# tally-controller-shield.net
KiCad netlist of a schematic drawn in EAGLE
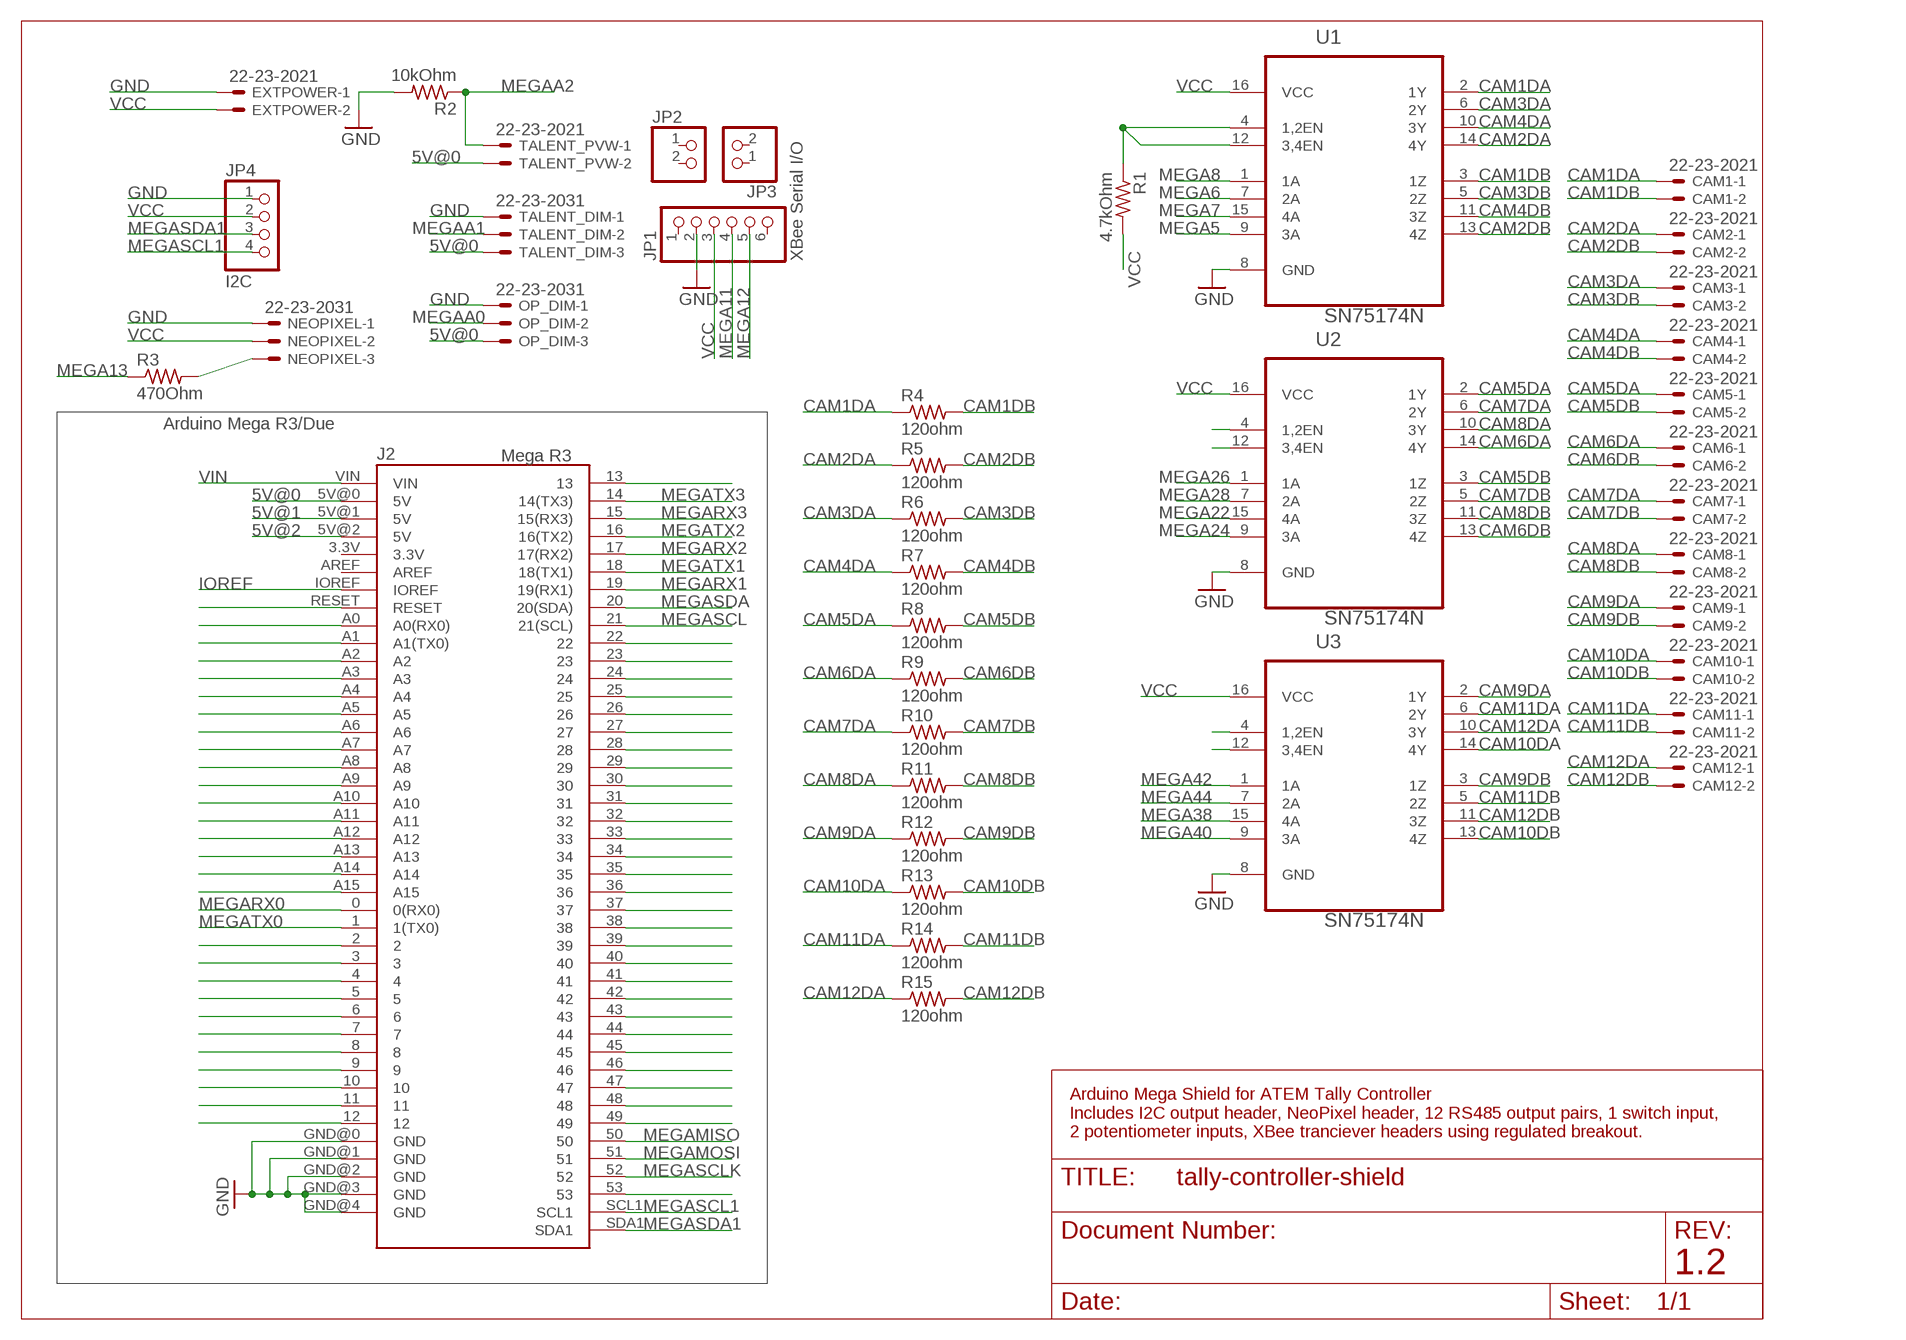
[diagram p0: schematic, sheet 1]

(export (version "E")
  (design (tool "Eeschema 10.0.6"))
  (components
    (comp (ref "CAM1")
      (value "22-23-2021")
      (footprint "eagle-import:22-23-2021")
      (fields (field (name "MF") "MOLEX"))
      (libsource (lib "eagle-import") (part "22-23-2021"))
    )
    (comp (ref "CAM2")
      (value "22-23-2021")
      (footprint "eagle-import:22-23-2021")
      (fields (field (name "MF") "MOLEX"))
      (libsource (lib "eagle-import") (part "22-23-2021"))
    )
    (comp (ref "CAM3")
      (value "22-23-2021")
      (footprint "eagle-import:22-23-2021")
      (fields (field (name "MF") "MOLEX"))
      (libsource (lib "eagle-import") (part "22-23-2021"))
    )
    (comp (ref "CAM4")
      (value "22-23-2021")
      (footprint "eagle-import:22-23-2021")
      (fields (field (name "MF") "MOLEX"))
      (libsource (lib "eagle-import") (part "22-23-2021"))
    )
    (comp (ref "CAM5")
      (value "22-23-2021")
      (footprint "eagle-import:22-23-2021")
      (fields (field (name "MF") "MOLEX"))
      (libsource (lib "eagle-import") (part "22-23-2021"))
    )
    (comp (ref "CAM6")
      (value "22-23-2021")
      (footprint "eagle-import:22-23-2021")
      (fields (field (name "MF") "MOLEX"))
      (libsource (lib "eagle-import") (part "22-23-2021"))
    )
    (comp (ref "CAM7")
      (value "22-23-2021")
      (footprint "eagle-import:22-23-2021")
      (fields (field (name "MF") "MOLEX"))
      (libsource (lib "eagle-import") (part "22-23-2021"))
    )
    (comp (ref "CAM8")
      (value "22-23-2021")
      (footprint "eagle-import:22-23-2021")
      (fields (field (name "MF") "MOLEX"))
      (libsource (lib "eagle-import") (part "22-23-2021"))
    )
    (comp (ref "CAM9")
      (value "22-23-2021")
      (footprint "eagle-import:22-23-2021")
      (fields (field (name "MF") "MOLEX"))
      (libsource (lib "eagle-import") (part "22-23-2021"))
    )
    (comp (ref "CAM10")
      (value "22-23-2021")
      (footprint "eagle-import:22-23-2021")
      (fields (field (name "MF") "MOLEX"))
      (libsource (lib "eagle-import") (part "22-23-2021"))
    )
    (comp (ref "CAM11")
      (value "22-23-2021")
      (footprint "eagle-import:22-23-2021")
      (fields (field (name "MF") "MOLEX"))
      (libsource (lib "eagle-import") (part "22-23-2021"))
    )
    (comp (ref "CAM12")
      (value "22-23-2021")
      (footprint "eagle-import:22-23-2021")
      (fields (field (name "MF") "MOLEX"))
      (libsource (lib "eagle-import") (part "22-23-2021"))
    )
    (comp (ref "EXTPOWER")
      (value "22-23-2021")
      (footprint "eagle-import:22-23-2021")
      (fields (field (name "MF") "MOLEX"))
      (libsource (lib "eagle-import") (part "22-23-2021"))
    )
    (comp (ref "J2")
      (value "Mega R3")
      (footprint "eagle-import:ARDUINO_MEGA")
      (libsource (lib "eagle-import") (part "ARDUINO-MEGAFULL"))
    )
    (comp (ref "JP1")
      (value "XBee Serial I/O")
      (footprint "eagle-import:1X06")
      (libsource (lib "eagle-import") (part "PINHD-1X6"))
    )
    (comp (ref "JP2")
      (value "PINHD-1X2")
      (footprint "eagle-import:1X02")
      (libsource (lib "eagle-import") (part "PINHD-1X2"))
    )
    (comp (ref "JP3")
      (value "PINHD-1X2")
      (footprint "eagle-import:1X02")
      (libsource (lib "eagle-import") (part "PINHD-1X2"))
    )
    (comp (ref "JP4")
      (value "I2C")
      (footprint "eagle-import:1X04")
      (libsource (lib "eagle-import") (part "PINHD-1X4"))
    )
    (comp (ref "NEOPIXEL")
      (value "22-23-2031")
      (footprint "eagle-import:22-23-2031")
      (fields (field (name "MF") "MOLEX"))
      (libsource (lib "eagle-import") (part "22-23-2031"))
    )
    (comp (ref "OP_DIM")
      (value "22-23-2031")
      (footprint "eagle-import:22-23-2031")
      (fields (field (name "MF") "MOLEX"))
      (libsource (lib "eagle-import") (part "22-23-2031"))
    )
    (comp (ref "R1")
      (value "4.7kOhm")
      (footprint "eagle-import:0207_10")
      (libsource (lib "eagle-import") (part "R-US_0207/10"))
    )
    (comp (ref "R2")
      (value "10kOhm")
      (footprint "eagle-import:0207_10")
      (libsource (lib "eagle-import") (part "R-US_0207/10"))
    )
    (comp (ref "R3")
      (value "470Ohm")
      (footprint "eagle-import:0207_10")
      (libsource (lib "eagle-import") (part "R-US_0207/10"))
    )
    (comp (ref "R4")
      (value "120ohm")
      (footprint "eagle-import:R0805")
      (libsource (lib "eagle-import") (part "R-US_R0805"))
    )
    (comp (ref "R5")
      (value "120ohm")
      (footprint "eagle-import:R0805")
      (libsource (lib "eagle-import") (part "R-US_R0805"))
    )
    (comp (ref "R6")
      (value "120ohm")
      (footprint "eagle-import:R0805")
      (libsource (lib "eagle-import") (part "R-US_R0805"))
    )
    (comp (ref "R7")
      (value "120ohm")
      (footprint "eagle-import:R0805")
      (libsource (lib "eagle-import") (part "R-US_R0805"))
    )
    (comp (ref "R8")
      (value "120ohm")
      (footprint "eagle-import:R0805")
      (libsource (lib "eagle-import") (part "R-US_R0805"))
    )
    (comp (ref "R9")
      (value "120ohm")
      (footprint "eagle-import:R0805")
      (libsource (lib "eagle-import") (part "R-US_R0805"))
    )
    (comp (ref "R10")
      (value "120ohm")
      (footprint "eagle-import:R0805")
      (libsource (lib "eagle-import") (part "R-US_R0805"))
    )
    (comp (ref "R11")
      (value "120ohm")
      (footprint "eagle-import:R0805")
      (libsource (lib "eagle-import") (part "R-US_R0805"))
    )
    (comp (ref "R12")
      (value "120ohm")
      (footprint "eagle-import:R0805")
      (libsource (lib "eagle-import") (part "R-US_R0805"))
    )
    (comp (ref "R13")
      (value "120ohm")
      (footprint "eagle-import:R0805")
      (libsource (lib "eagle-import") (part "R-US_R0805"))
    )
    (comp (ref "R14")
      (value "120ohm")
      (footprint "eagle-import:R0805")
      (libsource (lib "eagle-import") (part "R-US_R0805"))
    )
    (comp (ref "R15")
      (value "120ohm")
      (footprint "eagle-import:R0805")
      (libsource (lib "eagle-import") (part "R-US_R0805"))
    )
    (comp (ref "TALENT_DIM")
      (value "22-23-2031")
      (footprint "eagle-import:22-23-2031")
      (fields (field (name "MF") "MOLEX"))
      (libsource (lib "eagle-import") (part "22-23-2031"))
    )
    (comp (ref "TALENT_PVW")
      (value "22-23-2021")
      (footprint "eagle-import:22-23-2021")
      (fields (field (name "MF") "MOLEX"))
      (libsource (lib "eagle-import") (part "22-23-2021"))
    )
    (comp (ref "U1")
      (value "SN75174N")
      (footprint "eagle-import:DIP254P762X508-16")
      (fields (field (name "MF") "Texas Instruments"))
      (libsource (lib "eagle-import") (part "SN75174N"))
    )
    (comp (ref "U2")
      (value "SN75174N")
      (footprint "eagle-import:DIP254P762X508-16")
      (fields (field (name "MF") "Texas Instruments"))
      (libsource (lib "eagle-import") (part "SN75174N"))
    )
    (comp (ref "U3")
      (value "SN75174N")
      (footprint "eagle-import:DIP254P762X508-16")
      (fields (field (name "MF") "Texas Instruments"))
      (libsource (lib "eagle-import") (part "SN75174N"))
    )
  )
  (nets
    (net (code "1") (name "/5V@0") (class "Default")
      (node (ref "J2") (pin "5V@0") (pinfunction "5V_5V@0") (pintype "bidirectional"))
      (node (ref "OP_DIM") (pin "3") (pinfunction "S_3") (pintype "passive"))
      (node (ref "TALENT_DIM") (pin "3") (pinfunction "S_3") (pintype "passive"))
      (node (ref "TALENT_PVW") (pin "2") (pinfunction "S_2") (pintype "passive"))
    )
    (net (code "2") (name "/5V@1") (class "Default")
      (node (ref "J2") (pin "5V@1") (pinfunction "5V_5V@1") (pintype "bidirectional"))
    )
    (net (code "3") (name "/5V@2") (class "Default")
      (node (ref "J2") (pin "5V@2") (pinfunction "5V_5V@2") (pintype "bidirectional"))
    )
    (net (code "4") (name "/CAM1DA") (class "Default")
      (node (ref "CAM1") (pin "1") (pinfunction "S_1") (pintype "passive"))
      (node (ref "R4") (pin "1") (pinfunction "1_1") (pintype "passive"))
      (node (ref "U1") (pin "2") (pinfunction "1Y_2") (pintype "output"))
    )
    (net (code "5") (name "/CAM1DB") (class "Default")
      (node (ref "CAM1") (pin "2") (pinfunction "S_2") (pintype "passive"))
      (node (ref "R4") (pin "2") (pinfunction "2_2") (pintype "passive"))
      (node (ref "U1") (pin "3") (pinfunction "1Z_3") (pintype "output"))
    )
    (net (code "6") (name "/CAM2DA") (class "Default")
      (node (ref "CAM2") (pin "1") (pinfunction "S_1") (pintype "passive"))
      (node (ref "R5") (pin "1") (pinfunction "1_1") (pintype "passive"))
      (node (ref "U1") (pin "14") (pinfunction "4Y_14") (pintype "output"))
    )
    (net (code "7") (name "/CAM2DB") (class "Default")
      (node (ref "CAM2") (pin "2") (pinfunction "S_2") (pintype "passive"))
      (node (ref "R5") (pin "2") (pinfunction "2_2") (pintype "passive"))
      (node (ref "U1") (pin "13") (pinfunction "4Z_13") (pintype "output"))
    )
    (net (code "8") (name "/CAM3DA") (class "Default")
      (node (ref "CAM3") (pin "1") (pinfunction "S_1") (pintype "passive"))
      (node (ref "R6") (pin "1") (pinfunction "1_1") (pintype "passive"))
      (node (ref "U1") (pin "6") (pinfunction "2Y_6") (pintype "output"))
    )
    (net (code "9") (name "/CAM3DB") (class "Default")
      (node (ref "CAM3") (pin "2") (pinfunction "S_2") (pintype "passive"))
      (node (ref "R6") (pin "2") (pinfunction "2_2") (pintype "passive"))
      (node (ref "U1") (pin "5") (pinfunction "2Z_5") (pintype "output"))
    )
    (net (code "10") (name "/CAM4DA") (class "Default")
      (node (ref "CAM4") (pin "1") (pinfunction "S_1") (pintype "passive"))
      (node (ref "R7") (pin "1") (pinfunction "1_1") (pintype "passive"))
      (node (ref "U1") (pin "10") (pinfunction "3Y_10") (pintype "output"))
    )
    (net (code "11") (name "/CAM4DB") (class "Default")
      (node (ref "CAM4") (pin "2") (pinfunction "S_2") (pintype "passive"))
      (node (ref "R7") (pin "2") (pinfunction "2_2") (pintype "passive"))
      (node (ref "U1") (pin "11") (pinfunction "3Z_11") (pintype "output"))
    )
    (net (code "12") (name "/CAM5DA") (class "Default")
      (node (ref "CAM5") (pin "1") (pinfunction "S_1") (pintype "passive"))
      (node (ref "R8") (pin "1") (pinfunction "1_1") (pintype "passive"))
      (node (ref "U2") (pin "2") (pinfunction "1Y_2") (pintype "output"))
    )
    (net (code "13") (name "/CAM5DB") (class "Default")
      (node (ref "CAM5") (pin "2") (pinfunction "S_2") (pintype "passive"))
      (node (ref "R8") (pin "2") (pinfunction "2_2") (pintype "passive"))
      (node (ref "U2") (pin "3") (pinfunction "1Z_3") (pintype "output"))
    )
    (net (code "14") (name "/CAM6DA") (class "Default")
      (node (ref "CAM6") (pin "1") (pinfunction "S_1") (pintype "passive"))
      (node (ref "R9") (pin "1") (pinfunction "1_1") (pintype "passive"))
      (node (ref "U2") (pin "14") (pinfunction "4Y_14") (pintype "output"))
    )
    (net (code "15") (name "/CAM6DB") (class "Default")
      (node (ref "CAM6") (pin "2") (pinfunction "S_2") (pintype "passive"))
      (node (ref "R9") (pin "2") (pinfunction "2_2") (pintype "passive"))
      (node (ref "U2") (pin "13") (pinfunction "4Z_13") (pintype "output"))
    )
    (net (code "16") (name "/CAM7DA") (class "Default")
      (node (ref "CAM7") (pin "1") (pinfunction "S_1") (pintype "passive"))
      (node (ref "R10") (pin "1") (pinfunction "1_1") (pintype "passive"))
      (node (ref "U2") (pin "6") (pinfunction "2Y_6") (pintype "output"))
    )
    (net (code "17") (name "/CAM7DB") (class "Default")
      (node (ref "CAM7") (pin "2") (pinfunction "S_2") (pintype "passive"))
      (node (ref "R10") (pin "2") (pinfunction "2_2") (pintype "passive"))
      (node (ref "U2") (pin "5") (pinfunction "2Z_5") (pintype "output"))
    )
    (net (code "18") (name "/CAM8DA") (class "Default")
      (node (ref "CAM8") (pin "1") (pinfunction "S_1") (pintype "passive"))
      (node (ref "R11") (pin "1") (pinfunction "1_1") (pintype "passive"))
      (node (ref "U2") (pin "10") (pinfunction "3Y_10") (pintype "output"))
    )
    (net (code "19") (name "/CAM8DB") (class "Default")
      (node (ref "CAM8") (pin "2") (pinfunction "S_2") (pintype "passive"))
      (node (ref "R11") (pin "2") (pinfunction "2_2") (pintype "passive"))
      (node (ref "U2") (pin "11") (pinfunction "3Z_11") (pintype "output"))
    )
    (net (code "20") (name "/CAM9DA") (class "Default")
      (node (ref "CAM9") (pin "1") (pinfunction "S_1") (pintype "passive"))
      (node (ref "R12") (pin "1") (pinfunction "1_1") (pintype "passive"))
      (node (ref "U3") (pin "2") (pinfunction "1Y_2") (pintype "output"))
    )
    (net (code "21") (name "/CAM9DB") (class "Default")
      (node (ref "CAM9") (pin "2") (pinfunction "S_2") (pintype "passive"))
      (node (ref "R12") (pin "2") (pinfunction "2_2") (pintype "passive"))
      (node (ref "U3") (pin "3") (pinfunction "1Z_3") (pintype "output"))
    )
    (net (code "22") (name "/CAM10DA") (class "Default")
      (node (ref "CAM10") (pin "1") (pinfunction "S_1") (pintype "passive"))
      (node (ref "R13") (pin "1") (pinfunction "1_1") (pintype "passive"))
      (node (ref "U3") (pin "14") (pinfunction "4Y_14") (pintype "output"))
    )
    (net (code "23") (name "/CAM10DB") (class "Default")
      (node (ref "CAM10") (pin "2") (pinfunction "S_2") (pintype "passive"))
      (node (ref "R13") (pin "2") (pinfunction "2_2") (pintype "passive"))
      (node (ref "U3") (pin "13") (pinfunction "4Z_13") (pintype "output"))
    )
    (net (code "24") (name "/CAM11DA") (class "Default")
      (node (ref "CAM11") (pin "1") (pinfunction "S_1") (pintype "passive"))
      (node (ref "R14") (pin "1") (pinfunction "1_1") (pintype "passive"))
      (node (ref "U3") (pin "6") (pinfunction "2Y_6") (pintype "output"))
    )
    (net (code "25") (name "/CAM11DB") (class "Default")
      (node (ref "CAM11") (pin "2") (pinfunction "S_2") (pintype "passive"))
      (node (ref "R14") (pin "2") (pinfunction "2_2") (pintype "passive"))
      (node (ref "U3") (pin "5") (pinfunction "2Z_5") (pintype "output"))
    )
    (net (code "26") (name "/CAM12DA") (class "Default")
      (node (ref "CAM12") (pin "1") (pinfunction "S_1") (pintype "passive"))
      (node (ref "R15") (pin "1") (pinfunction "1_1") (pintype "passive"))
      (node (ref "U3") (pin "10") (pinfunction "3Y_10") (pintype "output"))
    )
    (net (code "27") (name "/CAM12DB") (class "Default")
      (node (ref "CAM12") (pin "2") (pinfunction "S_2") (pintype "passive"))
      (node (ref "R15") (pin "2") (pinfunction "2_2") (pintype "passive"))
      (node (ref "U3") (pin "11") (pinfunction "3Z_11") (pintype "output"))
    )
    (net (code "28") (name "/IOREF") (class "Default")
      (node (ref "J2") (pin "IOREF") (pinfunction "IOREF_IOREF") (pintype "bidirectional"))
    )
    (net (code "29") (name "/MEGA5") (class "Default")
      (node (ref "J2") (pin "5") (pinfunction "5_5") (pintype "bidirectional"))
      (node (ref "U1") (pin "9") (pinfunction "3A_9") (pintype "input"))
    )
    (net (code "30") (name "/MEGA6") (class "Default")
      (node (ref "J2") (pin "6") (pinfunction "6_6") (pintype "bidirectional"))
      (node (ref "U1") (pin "7") (pinfunction "2A_7") (pintype "input"))
    )
    (net (code "31") (name "/MEGA7") (class "Default")
      (node (ref "J2") (pin "7") (pinfunction "7_7") (pintype "bidirectional"))
      (node (ref "U1") (pin "15") (pinfunction "4A_15") (pintype "input"))
    )
    (net (code "32") (name "/MEGA8") (class "Default")
      (node (ref "J2") (pin "8") (pinfunction "8_8") (pintype "bidirectional"))
      (node (ref "U1") (pin "1") (pinfunction "1A_1") (pintype "input"))
    )
    (net (code "33") (name "/MEGA11") (class "Default")
      (node (ref "J2") (pin "11") (pinfunction "11_11") (pintype "bidirectional"))
      (node (ref "JP1") (pin "4") (pinfunction "4_4") (pintype "passive"))
    )
    (net (code "34") (name "/MEGA12") (class "Default")
      (node (ref "J2") (pin "12") (pinfunction "12_12") (pintype "bidirectional"))
      (node (ref "JP1") (pin "5") (pinfunction "5_5") (pintype "passive"))
    )
    (net (code "35") (name "/MEGA13") (class "Default")
      (node (ref "J2") (pin "13") (pinfunction "13_13") (pintype "bidirectional"))
      (node (ref "R3") (pin "1") (pinfunction "1_1") (pintype "passive"))
    )
    (net (code "36") (name "/MEGA22") (class "Default")
      (node (ref "J2") (pin "22") (pinfunction "22_22") (pintype "bidirectional"))
      (node (ref "U2") (pin "15") (pinfunction "4A_15") (pintype "input"))
    )
    (net (code "37") (name "/MEGA24") (class "Default")
      (node (ref "J2") (pin "24") (pinfunction "24_24") (pintype "bidirectional"))
      (node (ref "U2") (pin "9") (pinfunction "3A_9") (pintype "input"))
    )
    (net (code "38") (name "/MEGA26") (class "Default")
      (node (ref "J2") (pin "26") (pinfunction "26_26") (pintype "bidirectional"))
      (node (ref "U2") (pin "1") (pinfunction "1A_1") (pintype "input"))
    )
    (net (code "39") (name "/MEGA28") (class "Default")
      (node (ref "J2") (pin "28") (pinfunction "28_28") (pintype "bidirectional"))
      (node (ref "U2") (pin "7") (pinfunction "2A_7") (pintype "input"))
    )
    (net (code "40") (name "/MEGA38") (class "Default")
      (node (ref "J2") (pin "38") (pinfunction "38_38") (pintype "bidirectional"))
      (node (ref "U3") (pin "15") (pinfunction "4A_15") (pintype "input"))
    )
    (net (code "41") (name "/MEGA40") (class "Default")
      (node (ref "J2") (pin "40") (pinfunction "40_40") (pintype "bidirectional"))
      (node (ref "U3") (pin "9") (pinfunction "3A_9") (pintype "input"))
    )
    (net (code "42") (name "/MEGA42") (class "Default")
      (node (ref "J2") (pin "42") (pinfunction "42_42") (pintype "bidirectional"))
      (node (ref "U3") (pin "1") (pinfunction "1A_1") (pintype "input"))
    )
    (net (code "43") (name "/MEGA44") (class "Default")
      (node (ref "J2") (pin "44") (pinfunction "44_44") (pintype "bidirectional"))
      (node (ref "U3") (pin "7") (pinfunction "2A_7") (pintype "input"))
    )
    (net (code "44") (name "/MEGAA0") (class "Default")
      (node (ref "J2") (pin "A0") (pinfunction "A0(RX0)_A0") (pintype "bidirectional"))
      (node (ref "OP_DIM") (pin "2") (pinfunction "S_2") (pintype "passive"))
    )
    (net (code "45") (name "/MEGAA1") (class "Default")
      (node (ref "J2") (pin "A1") (pinfunction "A1(TX0)_A1") (pintype "bidirectional"))
      (node (ref "TALENT_DIM") (pin "2") (pinfunction "S_2") (pintype "passive"))
    )
    (net (code "46") (name "/MEGAA2") (class "Default")
      (node (ref "J2") (pin "A2") (pinfunction "A2_A2") (pintype "bidirectional"))
      (node (ref "R2") (pin "1") (pinfunction "1_1") (pintype "passive"))
      (node (ref "TALENT_PVW") (pin "1") (pinfunction "S_1") (pintype "passive"))
    )
    (net (code "47") (name "/MEGAMISO") (class "Default")
      (node (ref "J2") (pin "50") (pinfunction "50_50") (pintype "bidirectional"))
    )
    (net (code "48") (name "/MEGAMOSI") (class "Default")
      (node (ref "J2") (pin "51") (pinfunction "51_51") (pintype "bidirectional"))
    )
    (net (code "49") (name "/MEGARX0") (class "Default")
      (node (ref "J2") (pin "0") (pinfunction "0(RX0)_0") (pintype "bidirectional"))
    )
    (net (code "50") (name "/MEGARX1") (class "Default")
      (node (ref "J2") (pin "19") (pinfunction "19(RX1)_19") (pintype "bidirectional"))
    )
    (net (code "51") (name "/MEGARX2") (class "Default")
      (node (ref "J2") (pin "17") (pinfunction "17(RX2)_17") (pintype "bidirectional"))
    )
    (net (code "52") (name "/MEGARX3") (class "Default")
      (node (ref "J2") (pin "15") (pinfunction "15(RX3)_15") (pintype "bidirectional"))
    )
    (net (code "53") (name "/MEGASCL") (class "Default")
      (node (ref "J2") (pin "21") (pinfunction "21(SCL)_21") (pintype "bidirectional"))
    )
    (net (code "54") (name "/MEGASCL1") (class "Default")
      (node (ref "J2") (pin "SCL1") (pinfunction "SCL1_SCL1") (pintype "bidirectional"))
      (node (ref "JP4") (pin "4") (pinfunction "4_4") (pintype "passive"))
    )
    (net (code "55") (name "/MEGASCLK") (class "Default")
      (node (ref "J2") (pin "52") (pinfunction "52_52") (pintype "bidirectional"))
    )
    (net (code "56") (name "/MEGASDA") (class "Default")
      (node (ref "J2") (pin "20") (pinfunction "20(SDA)_20") (pintype "bidirectional"))
    )
    (net (code "57") (name "/MEGASDA1") (class "Default")
      (node (ref "J2") (pin "SDA1") (pinfunction "SDA1_SDA1") (pintype "bidirectional"))
      (node (ref "JP4") (pin "3") (pinfunction "3_3") (pintype "passive"))
    )
    (net (code "58") (name "/MEGATX0") (class "Default")
      (node (ref "J2") (pin "1") (pinfunction "1(TX0)_1") (pintype "bidirectional"))
    )
    (net (code "59") (name "/MEGATX1") (class "Default")
      (node (ref "J2") (pin "18") (pinfunction "18(TX1)_18") (pintype "bidirectional"))
    )
    (net (code "60") (name "/MEGATX2") (class "Default")
      (node (ref "J2") (pin "16") (pinfunction "16(TX2)_16") (pintype "bidirectional"))
    )
    (net (code "61") (name "/MEGATX3") (class "Default")
      (node (ref "J2") (pin "14") (pinfunction "14(TX3)_14") (pintype "bidirectional"))
    )
    (net (code "62") (name "/RS485EN") (class "Default")
      (node (ref "R1") (pin "1") (pinfunction "1_1") (pintype "passive"))
      (node (ref "U1") (pin "12") (pinfunction "3,4EN_12") (pintype "input"))
      (node (ref "U1") (pin "4") (pinfunction "1,2EN_4") (pintype "input"))
      (node (ref "U2") (pin "12") (pinfunction "3,4EN_12") (pintype "input"))
      (node (ref "U2") (pin "4") (pinfunction "1,2EN_4") (pintype "input"))
      (node (ref "U3") (pin "12") (pinfunction "3,4EN_12") (pintype "input"))
      (node (ref "U3") (pin "4") (pinfunction "1,2EN_4") (pintype "input"))
    )
    (net (code "63") (name "/VCC") (class "Default")
      (node (ref "EXTPOWER") (pin "2") (pinfunction "S_2") (pintype "passive"))
      (node (ref "JP1") (pin "3") (pinfunction "3_3") (pintype "passive"))
      (node (ref "JP4") (pin "2") (pinfunction "2_2") (pintype "passive"))
      (node (ref "NEOPIXEL") (pin "2") (pinfunction "S_2") (pintype "passive"))
      (node (ref "R1") (pin "2") (pinfunction "2_2") (pintype "passive"))
      (node (ref "U1") (pin "16") (pinfunction "VCC_16") (pintype "power_in"))
      (node (ref "U2") (pin "16") (pinfunction "VCC_16") (pintype "power_in"))
      (node (ref "U3") (pin "16") (pinfunction "VCC_16") (pintype "power_in"))
    )
    (net (code "64") (name "/VIN") (class "Default")
      (node (ref "J2") (pin "VIN") (pinfunction "VIN_VIN") (pintype "bidirectional"))
    )
    (net (code "65") (name "GND") (class "Default")
      (node (ref "EXTPOWER") (pin "1") (pinfunction "S_1") (pintype "passive"))
      (node (ref "J2") (pin "GND@0") (pinfunction "GND_GND@0") (pintype "bidirectional"))
      (node (ref "J2") (pin "GND@1") (pinfunction "GND_GND@1") (pintype "bidirectional"))
      (node (ref "J2") (pin "GND@2") (pinfunction "GND_GND@2") (pintype "bidirectional"))
      (node (ref "J2") (pin "GND@3") (pinfunction "GND_GND@3") (pintype "bidirectional"))
      (node (ref "J2") (pin "GND@4") (pinfunction "GND_GND@4") (pintype "bidirectional"))
      (node (ref "JP1") (pin "2") (pinfunction "2_2") (pintype "passive"))
      (node (ref "JP4") (pin "1") (pinfunction "1_1") (pintype "passive"))
      (node (ref "NEOPIXEL") (pin "1") (pinfunction "S_1") (pintype "passive"))
      (node (ref "OP_DIM") (pin "1") (pinfunction "S_1") (pintype "passive"))
      (node (ref "R2") (pin "2") (pinfunction "2_2") (pintype "passive"))
      (node (ref "TALENT_DIM") (pin "1") (pinfunction "S_1") (pintype "passive"))
      (node (ref "U1") (pin "8") (pinfunction "GND_8") (pintype "passive"))
      (node (ref "U2") (pin "8") (pinfunction "GND_8") (pintype "passive"))
      (node (ref "U3") (pin "8") (pinfunction "GND_8") (pintype "passive"))
    )
    (net (code "66") (name "Net-(NEOPIXELC-S)") (class "Default")
      (node (ref "NEOPIXEL") (pin "3") (pinfunction "S_3") (pintype "passive"))
      (node (ref "R3") (pin "2") (pinfunction "2_2") (pintype "passive"))
    )
    (net (code "67") (name "unconnected-(J2-Pad2)") (class "Default")
      (node (ref "J2") (pin "2") (pinfunction "2_2") (pintype "bidirectional"))
    )
    (net (code "68") (name "unconnected-(J2-Pad3)") (class "Default")
      (node (ref "J2") (pin "3") (pinfunction "3_3") (pintype "bidirectional"))
    )
    (net (code "69") (name "unconnected-(J2-Pad3.3V)") (class "Default")
      (node (ref "J2") (pin "3.3V") (pinfunction "3.3V_3.3V") (pintype "bidirectional"))
    )
    (net (code "70") (name "unconnected-(J2-Pad4)") (class "Default")
      (node (ref "J2") (pin "4") (pinfunction "4_4") (pintype "bidirectional"))
    )
    (net (code "71") (name "unconnected-(J2-Pad9)") (class "Default")
      (node (ref "J2") (pin "9") (pinfunction "9_9") (pintype "bidirectional"))
    )
    (net (code "72") (name "unconnected-(J2-Pad10)") (class "Default")
      (node (ref "J2") (pin "10") (pinfunction "10_10") (pintype "bidirectional"))
    )
    (net (code "73") (name "unconnected-(J2-Pad23)") (class "Default")
      (node (ref "J2") (pin "23") (pinfunction "23_23") (pintype "bidirectional"))
    )
    (net (code "74") (name "unconnected-(J2-Pad25)") (class "Default")
      (node (ref "J2") (pin "25") (pinfunction "25_25") (pintype "bidirectional"))
    )
    (net (code "75") (name "unconnected-(J2-Pad27)") (class "Default")
      (node (ref "J2") (pin "27") (pinfunction "27_27") (pintype "bidirectional"))
    )
    (net (code "76") (name "unconnected-(J2-Pad29)") (class "Default")
      (node (ref "J2") (pin "29") (pinfunction "29_29") (pintype "bidirectional"))
    )
    (net (code "77") (name "unconnected-(J2-Pad30)") (class "Default")
      (node (ref "J2") (pin "30") (pinfunction "30_30") (pintype "bidirectional"))
    )
    (net (code "78") (name "unconnected-(J2-Pad31)") (class "Default")
      (node (ref "J2") (pin "31") (pinfunction "31_31") (pintype "bidirectional"))
    )
    (net (code "79") (name "unconnected-(J2-Pad32)") (class "Default")
      (node (ref "J2") (pin "32") (pinfunction "32_32") (pintype "bidirectional"))
    )
    (net (code "80") (name "unconnected-(J2-Pad33)") (class "Default")
      (node (ref "J2") (pin "33") (pinfunction "33_33") (pintype "bidirectional"))
    )
    (net (code "81") (name "unconnected-(J2-Pad34)") (class "Default")
      (node (ref "J2") (pin "34") (pinfunction "34_34") (pintype "bidirectional"))
    )
    (net (code "82") (name "unconnected-(J2-Pad35)") (class "Default")
      (node (ref "J2") (pin "35") (pinfunction "35_35") (pintype "bidirectional"))
    )
    (net (code "83") (name "unconnected-(J2-Pad36)") (class "Default")
      (node (ref "J2") (pin "36") (pinfunction "36_36") (pintype "bidirectional"))
    )
    (net (code "84") (name "unconnected-(J2-Pad37)") (class "Default")
      (node (ref "J2") (pin "37") (pinfunction "37_37") (pintype "bidirectional"))
    )
    (net (code "85") (name "unconnected-(J2-Pad39)") (class "Default")
      (node (ref "J2") (pin "39") (pinfunction "39_39") (pintype "bidirectional"))
    )
    (net (code "86") (name "unconnected-(J2-Pad41)") (class "Default")
      (node (ref "J2") (pin "41") (pinfunction "41_41") (pintype "bidirectional"))
    )
    (net (code "87") (name "unconnected-(J2-Pad43)") (class "Default")
      (node (ref "J2") (pin "43") (pinfunction "43_43") (pintype "bidirectional"))
    )
    (net (code "88") (name "unconnected-(J2-Pad45)") (class "Default")
      (node (ref "J2") (pin "45") (pinfunction "45_45") (pintype "bidirectional"))
    )
    (net (code "89") (name "unconnected-(J2-Pad46)") (class "Default")
      (node (ref "J2") (pin "46") (pinfunction "46_46") (pintype "bidirectional"))
    )
    (net (code "90") (name "unconnected-(J2-Pad47)") (class "Default")
      (node (ref "J2") (pin "47") (pinfunction "47_47") (pintype "bidirectional"))
    )
    (net (code "91") (name "unconnected-(J2-Pad48)") (class "Default")
      (node (ref "J2") (pin "48") (pinfunction "48_48") (pintype "bidirectional"))
    )
    (net (code "92") (name "unconnected-(J2-Pad49)") (class "Default")
      (node (ref "J2") (pin "49") (pinfunction "49_49") (pintype "bidirectional"))
    )
    (net (code "93") (name "unconnected-(J2-Pad53)") (class "Default")
      (node (ref "J2") (pin "53") (pinfunction "53_53") (pintype "bidirectional"))
    )
    (net (code "94") (name "unconnected-(J2-PadA3)") (class "Default")
      (node (ref "J2") (pin "A3") (pinfunction "A3_A3") (pintype "bidirectional"))
    )
    (net (code "95") (name "unconnected-(J2-PadA4)") (class "Default")
      (node (ref "J2") (pin "A4") (pinfunction "A4_A4") (pintype "bidirectional"))
    )
    (net (code "96") (name "unconnected-(J2-PadA5)") (class "Default")
      (node (ref "J2") (pin "A5") (pinfunction "A5_A5") (pintype "bidirectional"))
    )
    (net (code "97") (name "unconnected-(J2-PadA6)") (class "Default")
      (node (ref "J2") (pin "A6") (pinfunction "A6_A6") (pintype "bidirectional"))
    )
    (net (code "98") (name "unconnected-(J2-PadA7)") (class "Default")
      (node (ref "J2") (pin "A7") (pinfunction "A7_A7") (pintype "bidirectional"))
    )
    (net (code "99") (name "unconnected-(J2-PadA8)") (class "Default")
      (node (ref "J2") (pin "A8") (pinfunction "A8_A8") (pintype "bidirectional"))
    )
    (net (code "100") (name "unconnected-(J2-PadA9)") (class "Default")
      (node (ref "J2") (pin "A9") (pinfunction "A9_A9") (pintype "bidirectional"))
    )
    (net (code "101") (name "unconnected-(J2-PadA10)") (class "Default")
      (node (ref "J2") (pin "A10") (pinfunction "A10_A10") (pintype "bidirectional"))
    )
    (net (code "102") (name "unconnected-(J2-PadA11)") (class "Default")
      (node (ref "J2") (pin "A11") (pinfunction "A11_A11") (pintype "bidirectional"))
    )
    (net (code "103") (name "unconnected-(J2-PadA12)") (class "Default")
      (node (ref "J2") (pin "A12") (pinfunction "A12_A12") (pintype "bidirectional"))
    )
    (net (code "104") (name "unconnected-(J2-PadA13)") (class "Default")
      (node (ref "J2") (pin "A13") (pinfunction "A13_A13") (pintype "bidirectional"))
    )
    (net (code "105") (name "unconnected-(J2-PadA14)") (class "Default")
      (node (ref "J2") (pin "A14") (pinfunction "A14_A14") (pintype "bidirectional"))
    )
    (net (code "106") (name "unconnected-(J2-PadA15)") (class "Default")
      (node (ref "J2") (pin "A15") (pinfunction "A15_A15") (pintype "bidirectional"))
    )
    (net (code "107") (name "unconnected-(J2-PadAREF)") (class "Default")
      (node (ref "J2") (pin "AREF") (pinfunction "AREF_AREF") (pintype "bidirectional"))
    )
    (net (code "108") (name "unconnected-(J2-PadRESET)") (class "Default")
      (node (ref "J2") (pin "RESET") (pinfunction "RESET_RESET") (pintype "bidirectional"))
    )
    (net (code "109") (name "unconnected-(JP1-Pad1)") (class "Default")
      (node (ref "JP1") (pin "1") (pinfunction "1_1") (pintype "passive"))
    )
    (net (code "110") (name "unconnected-(JP1-Pad6)") (class "Default")
      (node (ref "JP1") (pin "6") (pinfunction "6_6") (pintype "passive"))
    )
    (net (code "111") (name "unconnected-(JP2-Pad1)") (class "Default")
      (node (ref "JP2") (pin "1") (pinfunction "1_1") (pintype "passive"))
    )
    (net (code "112") (name "unconnected-(JP2-Pad2)") (class "Default")
      (node (ref "JP2") (pin "2") (pinfunction "2_2") (pintype "passive"))
    )
    (net (code "113") (name "unconnected-(JP3-Pad1)") (class "Default")
      (node (ref "JP3") (pin "1") (pinfunction "1_1") (pintype "passive"))
    )
    (net (code "114") (name "unconnected-(JP3-Pad2)") (class "Default")
      (node (ref "JP3") (pin "2") (pinfunction "2_2") (pintype "passive"))
    )
  )
)
